# ai_breakout_rpi_rshaped.net
KiCad netlist of a schematic drawn in EAGLE
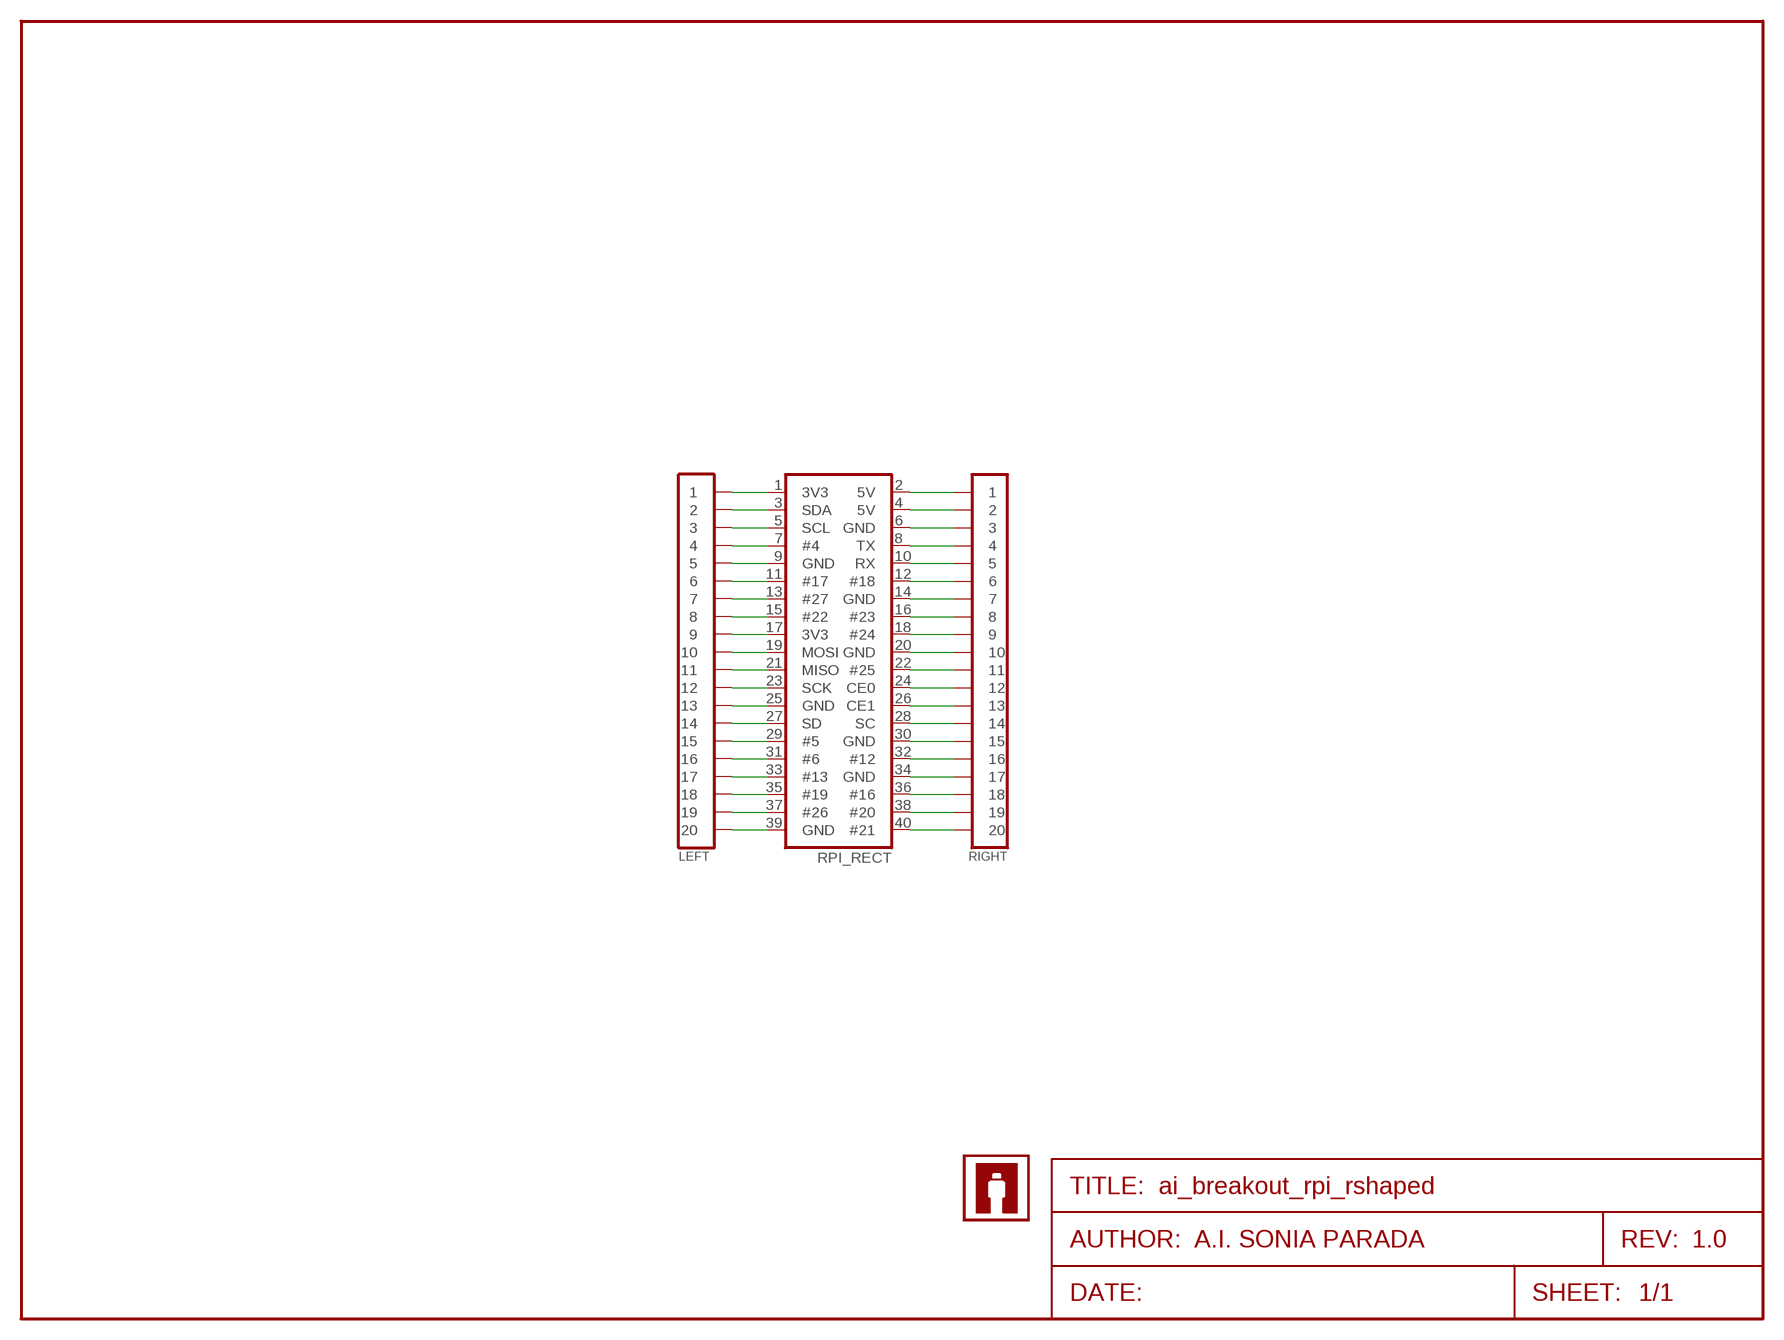
[diagram p0: schematic, sheet 1]

(export (version "E")
  (design (tool "Eeschema 10.0.6"))
  (components
    (comp (ref "LEFT")
      (value "1X20")
      (footprint "eagle-import:1X20")
      (libsource (lib "eagle-import") (part "1X20"))
    )
    (comp (ref "RIGHT")
      (value "1X20NOFIRST")
      (footprint "eagle-import:1X20-NOFIRST")
      (libsource (lib "eagle-import") (part "1X20NOFIRST"))
    )
    (comp (ref "RPI_RECT")
      (value "2X20-RPI-BRK")
      (footprint "eagle-import:2X20-RPI-BRK")
      (libsource (lib "eagle-import") (part "2X20-RPI-BRK"))
    )
    (comp (ref "U$1")
      (value "AI-LOGOXS")
      (footprint "eagle-import:AI-LOGO-XS")
      (libsource (lib "eagle-import") (part "AI-LOGOXS"))
    )
    (comp (ref "U$2")
      (value "AI-LOGOXS")
      (footprint "eagle-import:AI-LOGO-XS")
      (libsource (lib "eagle-import") (part "AI-LOGOXS"))
    )
  )
  (nets
    (net (code "1") (name "Net-(LEFT-Pad1)") (class "Default")
      (node (ref "LEFT") (pin "1") (pinfunction "1_1") (pintype "bidirectional"))
      (node (ref "RPI_RECT") (pin "1") (pinfunction "3V3_1") (pintype "bidirectional"))
    )
    (net (code "2") (name "Net-(LEFT-Pad5)") (class "Default")
      (node (ref "LEFT") (pin "5") (pinfunction "5_5") (pintype "bidirectional"))
      (node (ref "RPI_RECT") (pin "9") (pinfunction "GND_9") (pintype "bidirectional"))
    )
    (net (code "3") (name "Net-(LEFT-Pad9)") (class "Default")
      (node (ref "LEFT") (pin "9") (pinfunction "9_9") (pintype "bidirectional"))
      (node (ref "RPI_RECT") (pin "17") (pinfunction "3V3_17") (pintype "bidirectional"))
    )
    (net (code "4") (name "Net-(LEFT-Pad13)") (class "Default")
      (node (ref "LEFT") (pin "13") (pinfunction "13_13") (pintype "bidirectional"))
      (node (ref "RPI_RECT") (pin "25") (pinfunction "GND_25") (pintype "bidirectional"))
    )
    (net (code "5") (name "Net-(LEFT-Pad20)") (class "Default")
      (node (ref "LEFT") (pin "20") (pinfunction "20_20") (pintype "bidirectional"))
      (node (ref "RPI_RECT") (pin "39") (pinfunction "GND_39") (pintype "bidirectional"))
    )
    (net (code "6") (name "Net-(RIGHT-Pad1)") (class "Default")
      (node (ref "RIGHT") (pin "1") (pinfunction "1_1") (pintype "bidirectional"))
      (node (ref "RPI_RECT") (pin "2") (pinfunction "5V_2") (pintype "bidirectional"))
    )
    (net (code "7") (name "Net-(RIGHT-Pad2)") (class "Default")
      (node (ref "RIGHT") (pin "2") (pinfunction "2_2") (pintype "bidirectional"))
      (node (ref "RPI_RECT") (pin "4") (pinfunction "5V_4") (pintype "bidirectional"))
    )
    (net (code "8") (name "Net-(RIGHT-Pad3)") (class "Default")
      (node (ref "RIGHT") (pin "3") (pinfunction "3_3") (pintype "bidirectional"))
      (node (ref "RPI_RECT") (pin "6") (pinfunction "GND_6") (pintype "bidirectional"))
    )
    (net (code "9") (name "Net-(RIGHT-Pad7)") (class "Default")
      (node (ref "RIGHT") (pin "7") (pinfunction "7_7") (pintype "bidirectional"))
      (node (ref "RPI_RECT") (pin "14") (pinfunction "GND_14") (pintype "bidirectional"))
    )
    (net (code "10") (name "Net-(RIGHT-Pad10)") (class "Default")
      (node (ref "RIGHT") (pin "10") (pinfunction "10_10") (pintype "bidirectional"))
      (node (ref "RPI_RECT") (pin "20") (pinfunction "GND_20") (pintype "bidirectional"))
    )
    (net (code "11") (name "Net-(RIGHT-Pad15)") (class "Default")
      (node (ref "RIGHT") (pin "15") (pinfunction "15_15") (pintype "bidirectional"))
      (node (ref "RPI_RECT") (pin "30") (pinfunction "GND_30") (pintype "bidirectional"))
    )
    (net (code "12") (name "Net-(RIGHT-Pad17)") (class "Default")
      (node (ref "RIGHT") (pin "17") (pinfunction "17_17") (pintype "bidirectional"))
      (node (ref "RPI_RECT") (pin "34") (pinfunction "GND_34") (pintype "bidirectional"))
    )
    (net (code "13") (name "Net-(RPI_RECT-#4)") (class "Default")
      (node (ref "LEFT") (pin "4") (pinfunction "4_4") (pintype "bidirectional"))
      (node (ref "RPI_RECT") (pin "7") (pinfunction "#4_7") (pintype "bidirectional"))
    )
    (net (code "14") (name "Net-(RPI_RECT-#5)") (class "Default")
      (node (ref "LEFT") (pin "15") (pinfunction "15_15") (pintype "bidirectional"))
      (node (ref "RPI_RECT") (pin "29") (pinfunction "#5_29") (pintype "bidirectional"))
    )
    (net (code "15") (name "Net-(RPI_RECT-#6)") (class "Default")
      (node (ref "LEFT") (pin "16") (pinfunction "16_16") (pintype "bidirectional"))
      (node (ref "RPI_RECT") (pin "31") (pinfunction "#6_31") (pintype "bidirectional"))
    )
    (net (code "16") (name "Net-(RPI_RECT-#12)") (class "Default")
      (node (ref "RIGHT") (pin "16") (pinfunction "16_16") (pintype "bidirectional"))
      (node (ref "RPI_RECT") (pin "32") (pinfunction "#12_32") (pintype "bidirectional"))
    )
    (net (code "17") (name "Net-(RPI_RECT-#13)") (class "Default")
      (node (ref "LEFT") (pin "17") (pinfunction "17_17") (pintype "bidirectional"))
      (node (ref "RPI_RECT") (pin "33") (pinfunction "#13_33") (pintype "bidirectional"))
    )
    (net (code "18") (name "Net-(RPI_RECT-#16)") (class "Default")
      (node (ref "RIGHT") (pin "18") (pinfunction "18_18") (pintype "bidirectional"))
      (node (ref "RPI_RECT") (pin "36") (pinfunction "#16_36") (pintype "bidirectional"))
    )
    (net (code "19") (name "Net-(RPI_RECT-#17)") (class "Default")
      (node (ref "LEFT") (pin "6") (pinfunction "6_6") (pintype "bidirectional"))
      (node (ref "RPI_RECT") (pin "11") (pinfunction "#17_11") (pintype "bidirectional"))
    )
    (net (code "20") (name "Net-(RPI_RECT-#18)") (class "Default")
      (node (ref "RIGHT") (pin "6") (pinfunction "6_6") (pintype "bidirectional"))
      (node (ref "RPI_RECT") (pin "12") (pinfunction "#18_12") (pintype "bidirectional"))
    )
    (net (code "21") (name "Net-(RPI_RECT-#19)") (class "Default")
      (node (ref "LEFT") (pin "18") (pinfunction "18_18") (pintype "bidirectional"))
      (node (ref "RPI_RECT") (pin "35") (pinfunction "#19_35") (pintype "bidirectional"))
    )
    (net (code "22") (name "Net-(RPI_RECT-#20)") (class "Default")
      (node (ref "RIGHT") (pin "19") (pinfunction "19_19") (pintype "bidirectional"))
      (node (ref "RPI_RECT") (pin "38") (pinfunction "#20_38") (pintype "bidirectional"))
    )
    (net (code "23") (name "Net-(RPI_RECT-#21)") (class "Default")
      (node (ref "RIGHT") (pin "20") (pinfunction "20_20") (pintype "bidirectional"))
      (node (ref "RPI_RECT") (pin "40") (pinfunction "#21_40") (pintype "bidirectional"))
    )
    (net (code "24") (name "Net-(RPI_RECT-#22)") (class "Default")
      (node (ref "LEFT") (pin "8") (pinfunction "8_8") (pintype "bidirectional"))
      (node (ref "RPI_RECT") (pin "15") (pinfunction "#22_15") (pintype "bidirectional"))
    )
    (net (code "25") (name "Net-(RPI_RECT-#23)") (class "Default")
      (node (ref "RIGHT") (pin "8") (pinfunction "8_8") (pintype "bidirectional"))
      (node (ref "RPI_RECT") (pin "16") (pinfunction "#23_16") (pintype "bidirectional"))
    )
    (net (code "26") (name "Net-(RPI_RECT-#24)") (class "Default")
      (node (ref "RIGHT") (pin "9") (pinfunction "9_9") (pintype "bidirectional"))
      (node (ref "RPI_RECT") (pin "18") (pinfunction "#24_18") (pintype "bidirectional"))
    )
    (net (code "27") (name "Net-(RPI_RECT-#25)") (class "Default")
      (node (ref "RIGHT") (pin "11") (pinfunction "11_11") (pintype "bidirectional"))
      (node (ref "RPI_RECT") (pin "22") (pinfunction "#25_22") (pintype "bidirectional"))
    )
    (net (code "28") (name "Net-(RPI_RECT-#26)") (class "Default")
      (node (ref "LEFT") (pin "19") (pinfunction "19_19") (pintype "bidirectional"))
      (node (ref "RPI_RECT") (pin "37") (pinfunction "#26_37") (pintype "bidirectional"))
    )
    (net (code "29") (name "Net-(RPI_RECT-#27)") (class "Default")
      (node (ref "LEFT") (pin "7") (pinfunction "7_7") (pintype "bidirectional"))
      (node (ref "RPI_RECT") (pin "13") (pinfunction "#27_13") (pintype "bidirectional"))
    )
    (net (code "30") (name "Net-(RPI_RECT-CE0)") (class "Default")
      (node (ref "RIGHT") (pin "12") (pinfunction "12_12") (pintype "bidirectional"))
      (node (ref "RPI_RECT") (pin "24") (pinfunction "CE0_24") (pintype "bidirectional"))
    )
    (net (code "31") (name "Net-(RPI_RECT-CE1)") (class "Default")
      (node (ref "RIGHT") (pin "13") (pinfunction "13_13") (pintype "bidirectional"))
      (node (ref "RPI_RECT") (pin "26") (pinfunction "CE1_26") (pintype "bidirectional"))
    )
    (net (code "32") (name "Net-(RPI_RECT-MISO)") (class "Default")
      (node (ref "LEFT") (pin "11") (pinfunction "11_11") (pintype "bidirectional"))
      (node (ref "RPI_RECT") (pin "21") (pinfunction "MISO_21") (pintype "bidirectional"))
    )
    (net (code "33") (name "Net-(RPI_RECT-MOSI)") (class "Default")
      (node (ref "LEFT") (pin "10") (pinfunction "10_10") (pintype "bidirectional"))
      (node (ref "RPI_RECT") (pin "19") (pinfunction "MOSI_19") (pintype "bidirectional"))
    )
    (net (code "34") (name "Net-(RPI_RECT-RX)") (class "Default")
      (node (ref "RIGHT") (pin "5") (pinfunction "5_5") (pintype "bidirectional"))
      (node (ref "RPI_RECT") (pin "10") (pinfunction "RX_10") (pintype "bidirectional"))
    )
    (net (code "35") (name "Net-(RPI_RECT-SC)") (class "Default")
      (node (ref "RIGHT") (pin "14") (pinfunction "14_14") (pintype "bidirectional"))
      (node (ref "RPI_RECT") (pin "28") (pinfunction "SC_28") (pintype "bidirectional"))
    )
    (net (code "36") (name "Net-(RPI_RECT-SCK)") (class "Default")
      (node (ref "LEFT") (pin "12") (pinfunction "12_12") (pintype "bidirectional"))
      (node (ref "RPI_RECT") (pin "23") (pinfunction "SCK_23") (pintype "bidirectional"))
    )
    (net (code "37") (name "Net-(RPI_RECT-SCL)") (class "Default")
      (node (ref "LEFT") (pin "3") (pinfunction "3_3") (pintype "bidirectional"))
      (node (ref "RPI_RECT") (pin "5") (pinfunction "SCL_5") (pintype "bidirectional"))
    )
    (net (code "38") (name "Net-(RPI_RECT-SD)") (class "Default")
      (node (ref "LEFT") (pin "14") (pinfunction "14_14") (pintype "bidirectional"))
      (node (ref "RPI_RECT") (pin "27") (pinfunction "SD_27") (pintype "bidirectional"))
    )
    (net (code "39") (name "Net-(RPI_RECT-SDA)") (class "Default")
      (node (ref "LEFT") (pin "2") (pinfunction "2_2") (pintype "bidirectional"))
      (node (ref "RPI_RECT") (pin "3") (pinfunction "SDA_3") (pintype "bidirectional"))
    )
    (net (code "40") (name "Net-(RPI_RECT-TX)") (class "Default")
      (node (ref "RIGHT") (pin "4") (pinfunction "4_4") (pintype "bidirectional"))
      (node (ref "RPI_RECT") (pin "8") (pinfunction "TX_8") (pintype "bidirectional"))
    )
  )
)
